# RfLink-ESPlink.net
KiCad netlist of a schematic drawn in EAGLE
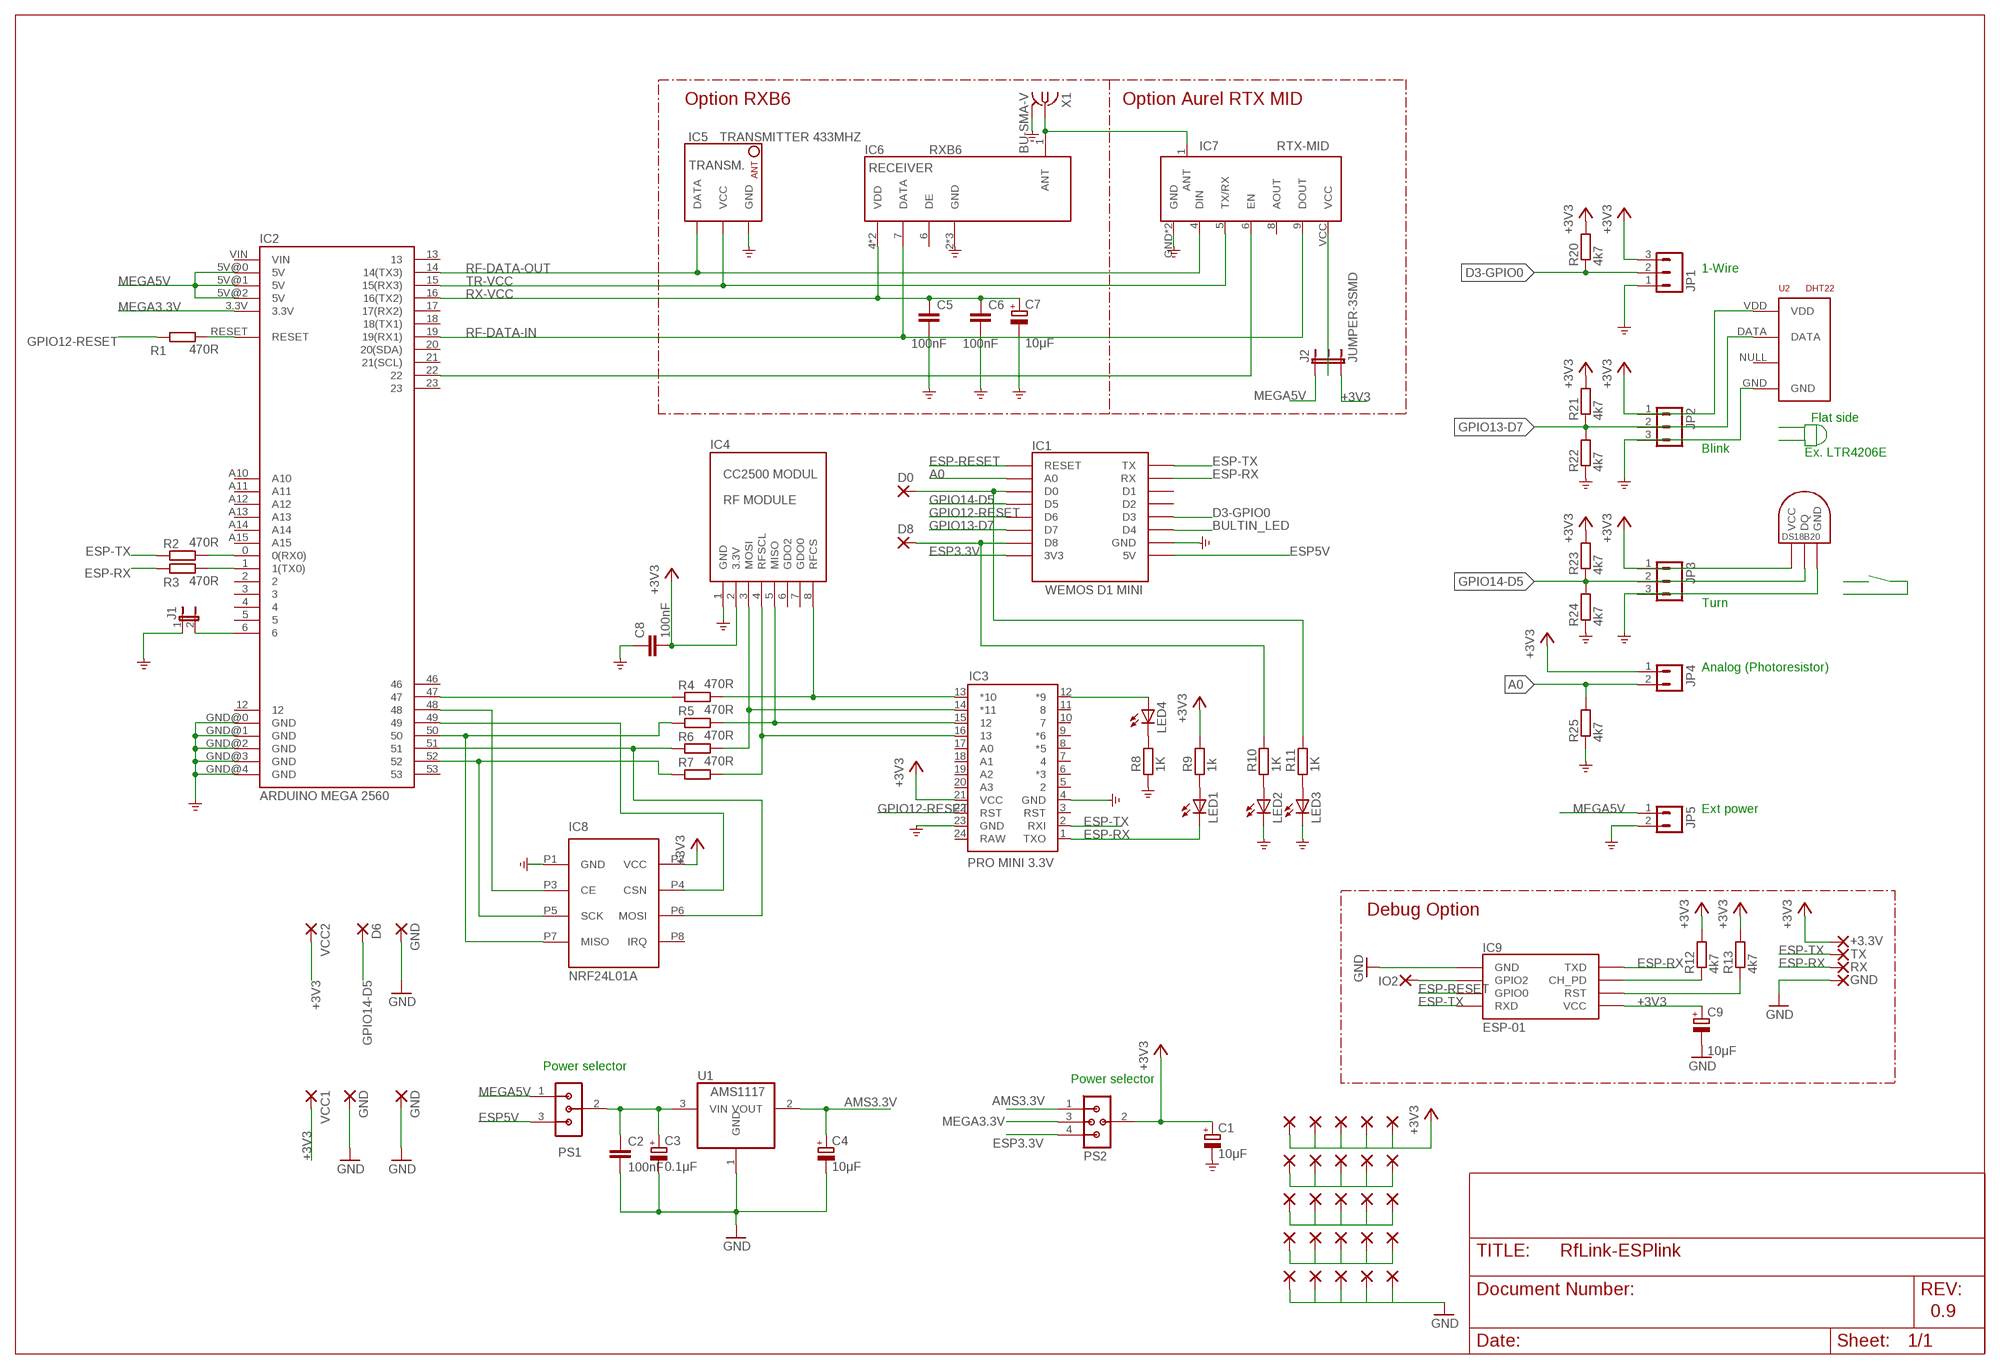
[diagram p0: schematic, sheet 1]

(export (version "E")
  (design (tool "Eeschema 10.0.6"))
  (components
    (comp (ref "+3.3V")
      (value "1,6/0,9")
      (footprint "eagle-import:1,6_0,9")
      (libsource (lib "eagle-import") (part "1,6/0,9"))
    )
    (comp (ref "C1")
      (value "10μF")
      (footprint "eagle-import:E2-5")
      (libsource (lib "eagle-import") (part "CPOL-EUE2-5"))
    )
    (comp (ref "C2")
      (value "100nF")
      (footprint "eagle-import:C0805")
      (libsource (lib "eagle-import") (part "CAPACITOR"))
    )
    (comp (ref "C3")
      (value "0.1μF")
      (footprint "eagle-import:E2-5")
      (libsource (lib "eagle-import") (part "CPOL-EUE2-5"))
    )
    (comp (ref "C4")
      (value "10μF")
      (footprint "eagle-import:E2-5")
      (libsource (lib "eagle-import") (part "CPOL-EUE2-5"))
    )
    (comp (ref "C5")
      (value "100nF")
      (footprint "eagle-import:C0805")
      (libsource (lib "eagle-import") (part "CAPACITOR"))
    )
    (comp (ref "C6")
      (value "100nF")
      (footprint "eagle-import:C0805")
      (libsource (lib "eagle-import") (part "CAPACITOR"))
    )
    (comp (ref "C7")
      (value "10μF")
      (footprint "eagle-import:E2-5")
      (libsource (lib "eagle-import") (part "CPOL-EUE2-5"))
    )
    (comp (ref "C8")
      (value "100nF")
      (footprint "eagle-import:C0805")
      (libsource (lib "eagle-import") (part "CAPACITOR"))
    )
    (comp (ref "C9")
      (value "10μF")
      (footprint "eagle-import:E2-5")
      (libsource (lib "eagle-import") (part "CPOL-EUE2-5"))
    )
    (comp (ref "D0")
      (value "1,6/0,9")
      (footprint "eagle-import:1,6_0,9")
      (libsource (lib "eagle-import") (part "1,6/0,9"))
    )
    (comp (ref "D6")
      (value "D6")
      (footprint "eagle-import:1,6_0,9")
      (libsource (lib "eagle-import") (part "1,6/0,9"))
    )
    (comp (ref "D8")
      (value "1,6/0,9")
      (footprint "eagle-import:1,6_0,9")
      (libsource (lib "eagle-import") (part "1,6/0,9"))
    )
    (comp (ref "G")
      (value "GND")
      (footprint "eagle-import:1,6_0,9")
      (libsource (lib "eagle-import") (part "1,6/0,9"))
    )
    (comp (ref "GND")
      (value "GND")
      (footprint "eagle-import:1,6_0,9")
      (libsource (lib "eagle-import") (part "1,6/0,9"))
    )
    (comp (ref "GND5")
      (value "GND")
      (footprint "eagle-import:1,6_0,9")
      (libsource (lib "eagle-import") (part "1,6/0,9"))
    )
    (comp (ref "GND7")
      (value "GND")
      (footprint "eagle-import:1,6_0,9")
      (libsource (lib "eagle-import") (part "1,6/0,9"))
    )
    (comp (ref "GPIO2")
      (value "IO2")
      (footprint "eagle-import:1,6_0,9")
      (libsource (lib "eagle-import") (part "1,6/0,9"))
    )
    (comp (ref "IC1")
      (value "WEMOS D1 MINI")
      (footprint "eagle-import:WEMOS-D1-MINI")
      (libsource (lib "eagle-import") (part "WEMOS-D1-MINI"))
    )
    (comp (ref "IC2")
      (value "ARDUINO MEGA 2560")
      (footprint "eagle-import:ARDUINO_MEGA_MINI")
      (libsource (lib "eagle-import") (part "ARDUINO-MEGA-MINI"))
    )
    (comp (ref "IC3")
      (value "PRO MINI 3.3V")
      (footprint "eagle-import:ARDUINO_PRO_MINI")
      (libsource (lib "eagle-import") (part "ARDUINO_PRO_MINI"))
    )
    (comp (ref "IC4")
      (value "CC2500 MODUL")
      (footprint "eagle-import:CC2500")
      (libsource (lib "eagle-import") (part "CC2500A-MODULE"))
    )
    (comp (ref "IC5")
      (value "TRANSMITTER 433MHZ")
      (footprint "eagle-import:TRANSMITTER433MHZ")
      (libsource (lib "eagle-import") (part "TRANSMITTER433MHZ"))
    )
    (comp (ref "IC6")
      (value "RXB6")
      (footprint "eagle-import:RXB6-LOW-SILKSCREEN")
      (libsource (lib "eagle-import") (part "HXB6-"))
    )
    (comp (ref "IC7")
      (value "RTX-MID")
      (footprint "eagle-import:RTX-MID")
      (libsource (lib "eagle-import") (part "RTX-MID"))
    )
    (comp (ref "IC8")
      (value "NRF24L01A")
      (footprint "eagle-import:NRF24L01")
      (libsource (lib "eagle-import") (part "NRF24L01A"))
    )
    (comp (ref "IC9")
      (value "ESP-01")
      (footprint "eagle-import:ESP01")
      (libsource (lib "eagle-import") (part "ESP01"))
    )
    (comp (ref "J1")
      (value "JUMPER-2SMD-NO")
      (footprint "eagle-import:SJ_2S-NO")
      (libsource (lib "eagle-import") (part "JUMPER-2SMD-NO"))
    )
    (comp (ref "J2")
      (value "JUMPER-3SMD")
      (footprint "eagle-import:SJ_3")
      (libsource (lib "eagle-import") (part "JUMPER-3SMD"))
    )
    (comp (ref "JP1")
      (value "GS015S-3.81-3P")
      (footprint "eagle-import:GS015S-3.81-3")
      (libsource (lib "eagle-import") (part "GS015S-3.81-3P"))
    )
    (comp (ref "JP2")
      (value "GS015S-3.81-3P")
      (footprint "eagle-import:GS015S-3.81-3")
      (libsource (lib "eagle-import") (part "GS015S-3.81-3P"))
    )
    (comp (ref "JP3")
      (value "GS015S-3.81-3P")
      (footprint "eagle-import:GS015S-3.81-3")
      (libsource (lib "eagle-import") (part "GS015S-3.81-3P"))
    )
    (comp (ref "JP4")
      (value "GS015S-3.81-2P")
      (footprint "eagle-import:GS015S-3.81-2")
      (libsource (lib "eagle-import") (part "GS015S-3.81-2P"))
    )
    (comp (ref "JP5")
      (value "GS015S-3.81-2P")
      (footprint "eagle-import:GS015S-3.81-2")
      (libsource (lib "eagle-import") (part "GS015S-3.81-2P"))
    )
    (comp (ref "LED1")
      (value "LED1206")
      (footprint "eagle-import:LED-1206")
      (libsource (lib "eagle-import") (part "LED1206"))
    )
    (comp (ref "LED2")
      (value "LED1206")
      (footprint "eagle-import:LED-1206")
      (libsource (lib "eagle-import") (part "LED1206"))
    )
    (comp (ref "LED3")
      (value "LED1206")
      (footprint "eagle-import:LED-1206")
      (libsource (lib "eagle-import") (part "LED1206"))
    )
    (comp (ref "LED4")
      (value "LED1206")
      (footprint "eagle-import:LED-1206")
      (libsource (lib "eagle-import") (part "LED1206"))
    )
    (comp (ref "P1")
      (value "1,6/0,9")
      (footprint "eagle-import:1,6_0,9")
      (libsource (lib "eagle-import") (part "1,6/0,9"))
    )
    (comp (ref "P2")
      (value "1,6/0,9")
      (footprint "eagle-import:1,6_0,9")
      (libsource (lib "eagle-import") (part "1,6/0,9"))
    )
    (comp (ref "P3")
      (value "1,6/0,9")
      (footprint "eagle-import:1,6_0,9")
      (libsource (lib "eagle-import") (part "1,6/0,9"))
    )
    (comp (ref "P4")
      (value "1,6/0,9")
      (footprint "eagle-import:1,6_0,9")
      (libsource (lib "eagle-import") (part "1,6/0,9"))
    )
    (comp (ref "P5")
      (value "1,6/0,9")
      (footprint "eagle-import:1,6_0,9")
      (libsource (lib "eagle-import") (part "1,6/0,9"))
    )
    (comp (ref "P6")
      (value "1,6/0,9")
      (footprint "eagle-import:1,6_0,9")
      (libsource (lib "eagle-import") (part "1,6/0,9"))
    )
    (comp (ref "P7")
      (value "1,6/0,9")
      (footprint "eagle-import:1,6_0,9")
      (libsource (lib "eagle-import") (part "1,6/0,9"))
    )
    (comp (ref "P8")
      (value "1,6/0,9")
      (footprint "eagle-import:1,6_0,9")
      (libsource (lib "eagle-import") (part "1,6/0,9"))
    )
    (comp (ref "P9")
      (value "1,6/0,9")
      (footprint "eagle-import:1,6_0,9")
      (libsource (lib "eagle-import") (part "1,6/0,9"))
    )
    (comp (ref "P10")
      (value "1,6/0,9")
      (footprint "eagle-import:1,6_0,9")
      (libsource (lib "eagle-import") (part "1,6/0,9"))
    )
    (comp (ref "P11")
      (value "1,6/0,9")
      (footprint "eagle-import:1,6_0,9")
      (libsource (lib "eagle-import") (part "1,6/0,9"))
    )
    (comp (ref "P12")
      (value "1,6/0,9")
      (footprint "eagle-import:1,6_0,9")
      (libsource (lib "eagle-import") (part "1,6/0,9"))
    )
    (comp (ref "P13")
      (value "1,6/0,9")
      (footprint "eagle-import:1,6_0,9")
      (libsource (lib "eagle-import") (part "1,6/0,9"))
    )
    (comp (ref "P14")
      (value "1,6/0,9")
      (footprint "eagle-import:1,6_0,9")
      (libsource (lib "eagle-import") (part "1,6/0,9"))
    )
    (comp (ref "P15")
      (value "1,6/0,9")
      (footprint "eagle-import:1,6_0,9")
      (libsource (lib "eagle-import") (part "1,6/0,9"))
    )
    (comp (ref "P16")
      (value "1,6/0,9")
      (footprint "eagle-import:1,6_0,9")
      (libsource (lib "eagle-import") (part "1,6/0,9"))
    )
    (comp (ref "P17")
      (value "1,6/0,9")
      (footprint "eagle-import:1,6_0,9")
      (libsource (lib "eagle-import") (part "1,6/0,9"))
    )
    (comp (ref "P18")
      (value "1,6/0,9")
      (footprint "eagle-import:1,6_0,9")
      (libsource (lib "eagle-import") (part "1,6/0,9"))
    )
    (comp (ref "P19")
      (value "1,6/0,9")
      (footprint "eagle-import:1,6_0,9")
      (libsource (lib "eagle-import") (part "1,6/0,9"))
    )
    (comp (ref "P20")
      (value "1,6/0,9")
      (footprint "eagle-import:1,6_0,9")
      (libsource (lib "eagle-import") (part "1,6/0,9"))
    )
    (comp (ref "P21")
      (value "1,6/0,9")
      (footprint "eagle-import:1,6_0,9")
      (libsource (lib "eagle-import") (part "1,6/0,9"))
    )
    (comp (ref "P22")
      (value "1,6/0,9")
      (footprint "eagle-import:1,6_0,9")
      (libsource (lib "eagle-import") (part "1,6/0,9"))
    )
    (comp (ref "P23")
      (value "1,6/0,9")
      (footprint "eagle-import:1,6_0,9")
      (libsource (lib "eagle-import") (part "1,6/0,9"))
    )
    (comp (ref "P24")
      (value "1,6/0,9")
      (footprint "eagle-import:1,6_0,9")
      (libsource (lib "eagle-import") (part "1,6/0,9"))
    )
    (comp (ref "P25")
      (value "1,6/0,9")
      (footprint "eagle-import:1,6_0,9")
      (libsource (lib "eagle-import") (part "1,6/0,9"))
    )
    (comp (ref "PS1")
      (value "SV2")
      (footprint "eagle-import:2-1")
      (libsource (lib "eagle-import") (part "2TO1POWER"))
    )
    (comp (ref "PS2")
      (value "3TO1POWER")
      (footprint "eagle-import:3-1")
      (libsource (lib "eagle-import") (part "3TO1POWER"))
    )
    (comp (ref "R1")
      (value "470R")
      (footprint "eagle-import:R0805")
      (libsource (lib "eagle-import") (part "RESISTORR0805"))
    )
    (comp (ref "R2")
      (value "470R")
      (footprint "eagle-import:R0805")
      (libsource (lib "eagle-import") (part "RESISTORR0805"))
    )
    (comp (ref "R3")
      (value "470R")
      (footprint "eagle-import:R0805")
      (libsource (lib "eagle-import") (part "RESISTORR0805"))
    )
    (comp (ref "R4")
      (value "470R")
      (footprint "eagle-import:R0805")
      (libsource (lib "eagle-import") (part "RESISTORR0805"))
    )
    (comp (ref "R5")
      (value "470R")
      (footprint "eagle-import:R0805")
      (libsource (lib "eagle-import") (part "RESISTORR0805"))
    )
    (comp (ref "R6")
      (value "470R")
      (footprint "eagle-import:R0805")
      (libsource (lib "eagle-import") (part "RESISTORR0805"))
    )
    (comp (ref "R7")
      (value "470R")
      (footprint "eagle-import:R0805")
      (libsource (lib "eagle-import") (part "RESISTORR0805"))
    )
    (comp (ref "R8")
      (value "1K")
      (footprint "eagle-import:R0805")
      (libsource (lib "eagle-import") (part "RESISTORR0805"))
    )
    (comp (ref "R9")
      (value "1k")
      (footprint "eagle-import:R0805")
      (libsource (lib "eagle-import") (part "RESISTORR0805"))
    )
    (comp (ref "R10")
      (value "1K")
      (footprint "eagle-import:R0805")
      (libsource (lib "eagle-import") (part "RESISTORR0805"))
    )
    (comp (ref "R11")
      (value "1K")
      (footprint "eagle-import:R0805")
      (libsource (lib "eagle-import") (part "RESISTORR0805"))
    )
    (comp (ref "R12")
      (value "4k7")
      (footprint "eagle-import:R0805")
      (libsource (lib "eagle-import") (part "RESISTORR0805"))
    )
    (comp (ref "R13")
      (value "4k7")
      (footprint "eagle-import:R0805")
      (libsource (lib "eagle-import") (part "RESISTORR0805"))
    )
    (comp (ref "R20")
      (value "4k7")
      (footprint "eagle-import:R0805")
      (libsource (lib "eagle-import") (part "RESISTORR0805"))
    )
    (comp (ref "R21")
      (value "4k7")
      (footprint "eagle-import:R0805")
      (libsource (lib "eagle-import") (part "RESISTORR0805"))
    )
    (comp (ref "R22")
      (value "4k7")
      (footprint "eagle-import:R0805")
      (libsource (lib "eagle-import") (part "RESISTORR0805"))
    )
    (comp (ref "R23")
      (value "4k7")
      (footprint "eagle-import:R0805")
      (libsource (lib "eagle-import") (part "RESISTORR0805"))
    )
    (comp (ref "R24")
      (value "4k7")
      (footprint "eagle-import:R0805")
      (libsource (lib "eagle-import") (part "RESISTORR0805"))
    )
    (comp (ref "R25")
      (value "4k7")
      (footprint "eagle-import:R0805")
      (libsource (lib "eagle-import") (part "RESISTORR0805"))
    )
    (comp (ref "RX")
      (value "RX")
      (footprint "eagle-import:1,6_0,9")
      (libsource (lib "eagle-import") (part "1,6/0,9"))
    )
    (comp (ref "TX")
      (value "TX")
      (footprint "eagle-import:1,6_0,9")
      (libsource (lib "eagle-import") (part "1,6/0,9"))
    )
    (comp (ref "U1")
      (value "AMS1117")
      (footprint "eagle-import:SOT223")
      (fields (field (name "MPN") "REG1117"))
      (libsource (lib "eagle-import") (part "REG1117"))
    )
    (comp (ref "U2")
      (value "DHT22")
      (footprint "eagle-import:RHT03_DHT-22")
      (libsource (lib "eagle-import") (part "RHT03_DHT-22_AM2302"))
    )
    (comp (ref "U3")
      (value "DS18B20")
      (footprint "eagle-import:DS1820")
      (libsource (lib "eagle-import") (part "DS1820TO92"))
    )
    (comp (ref "VCC1")
      (value "1,6/0,9")
      (footprint "eagle-import:1,6_0,9")
      (libsource (lib "eagle-import") (part "1,6/0,9"))
    )
    (comp (ref "VCC2")
      (value "1,6/0,9")
      (footprint "eagle-import:1,6_0,9")
      (libsource (lib "eagle-import") (part "1,6/0,9"))
    )
    (comp (ref "X1")
      (value "BU-SMA-V")
      (footprint "eagle-import:BU-SMA-V")
      (libsource (lib "eagle-import") (part "BU-SMA-V"))
    )
  )
  (nets
    (net (code "1") (name "+3V3") (class "Default")
      (node (ref "+3.3V") (pin "1") (pinfunction "P_1") (pintype "passive"))
      (node (ref "C1") (pin "+") (pinfunction "+_+") (pintype "passive"))
      (node (ref "C8") (pin "2") (pinfunction "2_2") (pintype "passive"))
      (node (ref "C9") (pin "+") (pinfunction "+_+") (pintype "passive"))
      (node (ref "IC3") (pin "21") (pinfunction "VCC_21") (pintype "bidirectional"))
      (node (ref "IC4") (pin "2") (pinfunction "3.3V_2") (pintype "bidirectional"))
      (node (ref "IC8") (pin "P2") (pinfunction "VCC_P2") (pintype "power_in"))
      (node (ref "IC9") (pin "VCC") (pinfunction "VCC_VCC") (pintype "bidirectional"))
      (node (ref "J2") (pin "3") (pinfunction "3_3") (pintype "passive"))
      (node (ref "JP1") (pin "3") (pinfunction "3_3") (pintype "passive"))
      (node (ref "JP2") (pin "1") (pinfunction "1_1") (pintype "passive"))
      (node (ref "JP3") (pin "1") (pinfunction "1_1") (pintype "passive"))
      (node (ref "JP4") (pin "1") (pinfunction "1_1") (pintype "passive"))
      (node (ref "P21") (pin "1") (pinfunction "P_1") (pintype "passive"))
      (node (ref "P22") (pin "1") (pinfunction "P_1") (pintype "passive"))
      (node (ref "P23") (pin "1") (pinfunction "P_1") (pintype "passive"))
      (node (ref "P24") (pin "1") (pinfunction "P_1") (pintype "passive"))
      (node (ref "P25") (pin "1") (pinfunction "P_1") (pintype "passive"))
      (node (ref "PS2") (pin "2") (pinfunction "2_2") (pintype "passive"))
      (node (ref "R12") (pin "2") (pinfunction "2_2") (pintype "passive"))
      (node (ref "R13") (pin "2") (pinfunction "2_2") (pintype "passive"))
      (node (ref "R20") (pin "2") (pinfunction "2_2") (pintype "passive"))
      (node (ref "R21") (pin "2") (pinfunction "2_2") (pintype "passive"))
      (node (ref "R23") (pin "2") (pinfunction "2_2") (pintype "passive"))
      (node (ref "R9") (pin "2") (pinfunction "2_2") (pintype "passive"))
      (node (ref "U2") (pin "VDD") (pinfunction "VDD_VDD") (pintype "power_in"))
      (node (ref "U3") (pin "VDD") (pinfunction "VCC_VDD") (pintype "power_in"))
      (node (ref "VCC1") (pin "1") (pinfunction "P_1") (pintype "passive"))
      (node (ref "VCC2") (pin "1") (pinfunction "P_1") (pintype "passive"))
    )
    (net (code "2") (name "/AMS3.3V") (class "Default")
      (node (ref "C4") (pin "+") (pinfunction "+_+") (pintype "passive"))
      (node (ref "PS2") (pin "1") (pinfunction "1_1") (pintype "passive"))
      (node (ref "U1") (pin "2") (pinfunction "VOUT_2") (pintype "output"))
    )
    (net (code "3") (name "/BULTIN_LED") (class "Default")
      (node (ref "IC1") (pin "D4") (pinfunction "D4_D4") (pintype "bidirectional"))
    )
    (net (code "4") (name "/ESP-RESET") (class "Default")
      (node (ref "IC1") (pin "RESET") (pinfunction "RESET_RESET") (pintype "bidirectional"))
      (node (ref "IC9") (pin "GPIO0") (pinfunction "GPIO0_GPIO0") (pintype "bidirectional"))
    )
    (net (code "5") (name "/ESP-RX") (class "Default")
      (node (ref "IC1") (pin "RX") (pinfunction "RX_RX") (pintype "bidirectional"))
      (node (ref "IC3") (pin "1") (pinfunction "TXO_1") (pintype "bidirectional"))
      (node (ref "IC9") (pin "TX") (pinfunction "TXD_TX") (pintype "bidirectional"))
      (node (ref "LED1") (pin "C") (pinfunction "C_C") (pintype "passive"))
      (node (ref "R3") (pin "1") (pinfunction "1_1") (pintype "passive"))
      (node (ref "RX") (pin "1") (pinfunction "P_1") (pintype "passive"))
    )
    (net (code "6") (name "/ESP-TX") (class "Default")
      (node (ref "IC1") (pin "TX") (pinfunction "TX_TX") (pintype "bidirectional"))
      (node (ref "IC3") (pin "2") (pinfunction "RXI_2") (pintype "bidirectional"))
      (node (ref "IC9") (pin "RX") (pinfunction "RXD_RX") (pintype "bidirectional"))
      (node (ref "R2") (pin "2") (pinfunction "2_2") (pintype "passive"))
      (node (ref "TX") (pin "1") (pinfunction "P_1") (pintype "passive"))
    )
    (net (code "7") (name "/ESP3.3V") (class "Default")
      (node (ref "IC1") (pin "3V3") (pinfunction "3V3_3V3") (pintype "bidirectional"))
      (node (ref "PS2") (pin "4") (pinfunction "4_4") (pintype "passive"))
    )
    (net (code "8") (name "/ESP5V") (class "Default")
      (node (ref "IC1") (pin "5V") (pinfunction "5V_5V") (pintype "bidirectional"))
      (node (ref "PS1") (pin "3") (pinfunction "3_3") (pintype "passive"))
    )
    (net (code "9") (name "/GPIO12-RESET") (class "Default")
      (node (ref "IC1") (pin "D6") (pinfunction "D6_D6") (pintype "bidirectional"))
      (node (ref "IC3") (pin "22") (pinfunction "RST_22") (pintype "bidirectional"))
      (node (ref "R1") (pin "2") (pinfunction "2_2") (pintype "passive"))
    )
    (net (code "10") (name "/MEGA3.3V") (class "Default")
      (node (ref "IC2") (pin "3.3V") (pinfunction "3.3V_3.3V") (pintype "bidirectional"))
      (node (ref "PS2") (pin "3") (pinfunction "3_3") (pintype "passive"))
    )
    (net (code "11") (name "/MEGA5V") (class "Default")
      (node (ref "IC2") (pin "5V@0") (pinfunction "5V_5V@0") (pintype "bidirectional"))
      (node (ref "IC2") (pin "5V@1") (pinfunction "5V_5V@1") (pintype "bidirectional"))
      (node (ref "IC2") (pin "5V@2") (pinfunction "5V_5V@2") (pintype "bidirectional"))
      (node (ref "J2") (pin "1") (pinfunction "1_1") (pintype "passive"))
      (node (ref "JP5") (pin "1") (pinfunction "1_1") (pintype "passive"))
      (node (ref "PS1") (pin "1") (pinfunction "1_1") (pintype "passive"))
    )
    (net (code "12") (name "/RF-DATA-IN") (class "Default")
      (node (ref "IC2") (pin "19") (pinfunction "19(RX1)_19") (pintype "bidirectional"))
      (node (ref "IC6") (pin "7") (pinfunction "DATA_7") (pintype "input"))
      (node (ref "IC7") (pin "9") (pinfunction "DOUT_9") (pintype "passive"))
    )
    (net (code "13") (name "/RF-DATA-OUT") (class "Default")
      (node (ref "IC2") (pin "14") (pinfunction "14(TX3)_14") (pintype "bidirectional"))
      (node (ref "IC5") (pin "P$1") (pinfunction "DATA_P$1") (pintype "input"))
      (node (ref "IC7") (pin "4") (pinfunction "DIN_4") (pintype "input"))
    )
    (net (code "14") (name "/RX-VCC") (class "Default")
      (node (ref "C5") (pin "2") (pinfunction "2_2") (pintype "passive"))
      (node (ref "C6") (pin "2") (pinfunction "2_2") (pintype "passive"))
      (node (ref "C7") (pin "+") (pinfunction "+_+") (pintype "passive"))
      (node (ref "IC2") (pin "16") (pinfunction "16(TX2)_16") (pintype "bidirectional"))
      (node (ref "IC6") (pin "4") (pinfunction "VDD_4") (pintype "power_in"))
      (node (ref "IC6") (pin "5") (pinfunction "VDD_5") (pintype "power_in"))
    )
    (net (code "15") (name "/TR-VCC") (class "Default")
      (node (ref "IC2") (pin "15") (pinfunction "15(RX3)_15") (pintype "bidirectional"))
      (node (ref "IC5") (pin "P$2") (pinfunction "VCC_P$2") (pintype "power_in"))
      (node (ref "IC7") (pin "5") (pinfunction "TX/RX_5") (pintype "passive"))
    )
    (net (code "16") (name "A0") (class "Default")
      (node (ref "IC1") (pin "A0") (pinfunction "A0_A0") (pintype "bidirectional"))
      (node (ref "JP4") (pin "2") (pinfunction "2_2") (pintype "passive"))
      (node (ref "R25") (pin "2") (pinfunction "2_2") (pintype "passive"))
    )
    (net (code "17") (name "D3-GPIO0") (class "Default")
      (node (ref "IC1") (pin "D3") (pinfunction "D3_D3") (pintype "bidirectional"))
      (node (ref "JP1") (pin "2") (pinfunction "2_2") (pintype "passive"))
      (node (ref "R20") (pin "1") (pinfunction "1_1") (pintype "passive"))
    )
    (net (code "18") (name "GND") (class "Default")
      (node (ref "C1") (pin "-") (pinfunction "-_-") (pintype "passive"))
      (node (ref "C2") (pin "2") (pinfunction "2_2") (pintype "passive"))
      (node (ref "C3") (pin "-") (pinfunction "-_-") (pintype "passive"))
      (node (ref "C4") (pin "-") (pinfunction "-_-") (pintype "passive"))
      (node (ref "C5") (pin "1") (pinfunction "1_1") (pintype "passive"))
      (node (ref "C6") (pin "1") (pinfunction "1_1") (pintype "passive"))
      (node (ref "C7") (pin "-") (pinfunction "-_-") (pintype "passive"))
      (node (ref "C8") (pin "1") (pinfunction "1_1") (pintype "passive"))
      (node (ref "C9") (pin "-") (pinfunction "-_-") (pintype "passive"))
      (node (ref "G") (pin "1") (pinfunction "P_1") (pintype "passive"))
      (node (ref "GND") (pin "1") (pinfunction "P_1") (pintype "passive"))
      (node (ref "GND5") (pin "1") (pinfunction "P_1") (pintype "passive"))
      (node (ref "GND7") (pin "1") (pinfunction "P_1") (pintype "passive"))
      (node (ref "IC1") (pin "GND") (pinfunction "GND_GND") (pintype "bidirectional"))
      (node (ref "IC2") (pin "GND@0") (pinfunction "GND_GND@0") (pintype "bidirectional"))
      (node (ref "IC2") (pin "GND@1") (pinfunction "GND_GND@1") (pintype "bidirectional"))
      (node (ref "IC2") (pin "GND@2") (pinfunction "GND_GND@2") (pintype "bidirectional"))
      (node (ref "IC2") (pin "GND@3") (pinfunction "GND_GND@3") (pintype "bidirectional"))
      (node (ref "IC2") (pin "GND@4") (pinfunction "GND_GND@4") (pintype "bidirectional"))
      (node (ref "IC3") (pin "23") (pinfunction "GND_23") (pintype "bidirectional"))
      (node (ref "IC3") (pin "4") (pinfunction "GND_4") (pintype "bidirectional"))
      (node (ref "IC4") (pin "1") (pinfunction "GND_1") (pintype "bidirectional"))
      (node (ref "IC5") (pin "P$3") (pinfunction "GND_P$3") (pintype "power_in"))
      (node (ref "IC6") (pin "2") (pinfunction "GND_2") (pintype "power_in"))
      (node (ref "IC6") (pin "3") (pinfunction "GND_3") (pintype "power_in"))
      (node (ref "IC6") (pin "8") (pinfunction "GND_8") (pintype "power_in"))
      (node (ref "IC7") (pin "GND") (pinfunction "GND_GND") (pintype "passive"))
      (node (ref "IC7") (pin "GND1") (pinfunction "GND_GND1") (pintype "passive"))
      (node (ref "IC8") (pin "P1") (pinfunction "GND_P1") (pintype "input"))
      (node (ref "IC9") (pin "GND") (pinfunction "GND_GND") (pintype "bidirectional"))
      (node (ref "J1") (pin "1") (pinfunction "1_1") (pintype "passive"))
      (node (ref "JP1") (pin "1") (pinfunction "1_1") (pintype "passive"))
      (node (ref "JP2") (pin "3") (pinfunction "3_3") (pintype "passive"))
      (node (ref "JP3") (pin "3") (pinfunction "3_3") (pintype "passive"))
      (node (ref "JP5") (pin "2") (pinfunction "2_2") (pintype "passive"))
      (node (ref "LED2") (pin "C") (pinfunction "C_C") (pintype "passive"))
      (node (ref "LED3") (pin "C") (pinfunction "C_C") (pintype "passive"))
      (node (ref "P11") (pin "1") (pinfunction "P_1") (pintype "passive"))
      (node (ref "P12") (pin "1") (pinfunction "P_1") (pintype "passive"))
      (node (ref "P13") (pin "1") (pinfunction "P_1") (pintype "passive"))
      (node (ref "P14") (pin "1") (pinfunction "P_1") (pintype "passive"))
      (node (ref "P15") (pin "1") (pinfunction "P_1") (pintype "passive"))
      (node (ref "R22") (pin "1") (pinfunction "1_1") (pintype "passive"))
      (node (ref "R24") (pin "1") (pinfunction "1_1") (pintype "passive"))
      (node (ref "R25") (pin "1") (pinfunction "1_1") (pintype "passive"))
      (node (ref "R8") (pin "1") (pinfunction "1_1") (pintype "passive"))
      (node (ref "U1") (pin "1") (pinfunction "GND_1") (pintype "power_in"))
      (node (ref "U2") (pin "GND") (pinfunction "GND_GND") (pintype "power_in"))
      (node (ref "U3") (pin "GND") (pinfunction "GND_GND") (pintype "power_in"))
      (node (ref "X1") (pin "2") (pinfunction "2_2") (pintype "passive"))
      (node (ref "X1") (pin "3") (pinfunction "2_3") (pintype "passive"))
      (node (ref "X1") (pin "4") (pinfunction "2_4") (pintype "passive"))
      (node (ref "X1") (pin "5") (pinfunction "2_5") (pintype "passive"))
    )
    (net (code "19") (name "GPIO13-D7") (class "Default")
      (node (ref "IC1") (pin "D7") (pinfunction "D7_D7") (pintype "bidirectional"))
      (node (ref "JP2") (pin "2") (pinfunction "2_2") (pintype "passive"))
      (node (ref "R21") (pin "1") (pinfunction "1_1") (pintype "passive"))
      (node (ref "R22") (pin "2") (pinfunction "2_2") (pintype "passive"))
      (node (ref "U2") (pin "DATA") (pinfunction "DATA_DATA") (pintype "bidirectional"))
    )
    (net (code "20") (name "GPIO14-D5") (class "Default")
      (node (ref "D6") (pin "1") (pinfunction "P_1") (pintype "passive"))
      (node (ref "IC1") (pin "D5") (pinfunction "D5_D5") (pintype "bidirectional"))
      (node (ref "JP3") (pin "2") (pinfunction "2_2") (pintype "passive"))
      (node (ref "R23") (pin "1") (pinfunction "1_1") (pintype "passive"))
      (node (ref "R24") (pin "2") (pinfunction "2_2") (pintype "passive"))
      (node (ref "U3") (pin "DQ") (pinfunction "DQ_DQ") (pintype "bidirectional"))
    )
    (net (code "21") (name "Net-(D0-P)") (class "Default")
      (node (ref "D0") (pin "1") (pinfunction "P_1") (pintype "passive"))
      (node (ref "IC1") (pin "D0") (pinfunction "D0_D0") (pintype "bidirectional"))
      (node (ref "R11") (pin "2") (pinfunction "2_2") (pintype "passive"))
    )
    (net (code "22") (name "Net-(D8-P)") (class "Default")
      (node (ref "D8") (pin "1") (pinfunction "P_1") (pintype "passive"))
      (node (ref "IC1") (pin "D8") (pinfunction "D8_D8") (pintype "bidirectional"))
      (node (ref "R10") (pin "2") (pinfunction "2_2") (pintype "passive"))
    )
    (net (code "23") (name "Net-(GPIO2-P)") (class "Default")
      (node (ref "GPIO2") (pin "1") (pinfunction "P_1") (pintype "passive"))
      (node (ref "IC9") (pin "GPIO2") (pinfunction "GPIO2_GPIO2") (pintype "bidirectional"))
    )
    (net (code "24") (name "Net-(IC2-0(RX0))") (class "Default")
      (node (ref "IC2") (pin "0") (pinfunction "0(RX0)_0") (pintype "bidirectional"))
      (node (ref "R2") (pin "1") (pinfunction "1_1") (pintype "passive"))
    )
    (net (code "25") (name "Net-(IC2-1(TX0))") (class "Default")
      (node (ref "IC2") (pin "1") (pinfunction "1(TX0)_1") (pintype "bidirectional"))
      (node (ref "R3") (pin "2") (pinfunction "2_2") (pintype "passive"))
    )
    (net (code "26") (name "Net-(IC2-Pad6)") (class "Default")
      (node (ref "IC2") (pin "6") (pinfunction "6_6") (pintype "bidirectional"))
      (node (ref "J1") (pin "2") (pinfunction "2_2") (pintype "passive"))
    )
    (net (code "27") (name "Net-(IC2-Pad47)") (class "Default")
      (node (ref "IC2") (pin "47") (pinfunction "47_47") (pintype "bidirectional"))
      (node (ref "R4") (pin "1") (pinfunction "1_1") (pintype "passive"))
    )
    (net (code "28") (name "Net-(IC2-PadRESET)") (class "Default")
      (node (ref "IC2") (pin "RESET") (pinfunction "RESET_RESET") (pintype "bidirectional"))
      (node (ref "R1") (pin "1") (pinfunction "1_1") (pintype "passive"))
    )
    (net (code "29") (name "Net-(IC3-*9)") (class "Default")
      (node (ref "IC3") (pin "12") (pinfunction "*9_12") (pintype "bidirectional"))
      (node (ref "LED4") (pin "A") (pinfunction "A_A") (pintype "passive"))
    )
    (net (code "30") (name "Net-(IC3-*10)") (class "Default")
      (node (ref "IC3") (pin "13") (pinfunction "*10_13") (pintype "bidirectional"))
      (node (ref "IC4") (pin "8") (pinfunction "RFCS_8") (pintype "bidirectional"))
      (node (ref "R4") (pin "2") (pinfunction "2_2") (pintype "passive"))
    )
    (net (code "31") (name "Net-(IC3-*11)") (class "Default")
      (node (ref "IC3") (pin "14") (pinfunction "*11_14") (pintype "bidirectional"))
      (node (ref "IC4") (pin "3") (pinfunction "MOSI_3") (pintype "bidirectional"))
      (node (ref "R6") (pin "2") (pinfunction "2_2") (pintype "passive"))
    )
    (net (code "32") (name "Net-(IC3-12)") (class "Default")
      (node (ref "IC3") (pin "15") (pinfunction "12_15") (pintype "bidirectional"))
      (node (ref "IC4") (pin "5") (pinfunction "MISO_5") (pintype "bidirectional"))
      (node (ref "R5") (pin "2") (pinfunction "2_2") (pintype "passive"))
    )
    (net (code "33") (name "Net-(IC3-13)") (class "Default")
      (node (ref "IC3") (pin "16") (pinfunction "13_16") (pintype "bidirectional"))
      (node (ref "IC4") (pin "4") (pinfunction "RFSCL_4") (pintype "bidirectional"))
      (node (ref "R7") (pin "2") (pinfunction "2_2") (pintype "passive"))
    )
    (net (code "34") (name "Net-(IC6-ANT)") (class "Default")
      (node (ref "IC6") (pin "1") (pinfunction "ANT_1") (pintype "output"))
      (node (ref "IC7") (pin "1") (pinfunction "ANT_1") (pintype "passive"))
      (node (ref "X1") (pin "1") (pinfunction "1_1") (pintype "passive"))
    )
    (net (code "35") (name "Net-(IC7-EN)") (class "Default")
      (node (ref "IC2") (pin "22") (pinfunction "22_22") (pintype "bidirectional"))
      (node (ref "IC7") (pin "6") (pinfunction "EN_6") (pintype "passive"))
    )
    (net (code "36") (name "Net-(IC7-PadVCC)") (class "Default")
      (node (ref "IC7") (pin "VCC") (pinfunction "VCC_VCC") (pintype "passive"))
      (node (ref "J2") (pin "2") (pinfunction "2_2") (pintype "passive"))
    )
    (net (code "37") (name "Net-(IC8-CE)") (class "Default")
      (node (ref "IC2") (pin "48") (pinfunction "48_48") (pintype "bidirectional"))
      (node (ref "IC8") (pin "P3") (pinfunction "CE_P3") (pintype "bidirectional"))
    )
    (net (code "38") (name "Net-(IC8-CSN)") (class "Default")
      (node (ref "IC2") (pin "49") (pinfunction "49_49") (pintype "bidirectional"))
      (node (ref "IC8") (pin "P4") (pinfunction "CSN_P4") (pintype "bidirectional"))
    )
    (net (code "39") (name "Net-(IC8-MISO)") (class "Default")
      (node (ref "IC2") (pin "50") (pinfunction "50_50") (pintype "bidirectional"))
      (node (ref "IC8") (pin "P7") (pinfunction "MISO_P7") (pintype "bidirectional"))
      (node (ref "R5") (pin "1") (pinfunction "1_1") (pintype "passive"))
    )
    (net (code "40") (name "Net-(IC8-MOSI)") (class "Default")
      (node (ref "IC2") (pin "51") (pinfunction "51_51") (pintype "bidirectional"))
      (node (ref "IC8") (pin "P6") (pinfunction "MOSI_P6") (pintype "bidirectional"))
      (node (ref "R6") (pin "1") (pinfunction "1_1") (pintype "passive"))
    )
    (net (code "41") (name "Net-(IC8-SCK)") (class "Default")
      (node (ref "IC2") (pin "52") (pinfunction "52_52") (pintype "bidirectional"))
      (node (ref "IC8") (pin "P5") (pinfunction "SCK_P5") (pintype "bidirectional"))
      (node (ref "R7") (pin "1") (pinfunction "1_1") (pintype "passive"))
    )
    (net (code "42") (name "Net-(IC9-PadCH_PD)") (class "Default")
      (node (ref "IC9") (pin "CH_PD") (pinfunction "CH_PD_CH_PD") (pintype "bidirectional"))
      (node (ref "R12") (pin "1") (pinfunction "1_1") (pintype "passive"))
    )
    (net (code "43") (name "Net-(IC9-PadRST)") (class "Default")
      (node (ref "IC9") (pin "RST") (pinfunction "RST_RST") (pintype "bidirectional"))
      (node (ref "R13") (pin "1") (pinfunction "1_1") (pintype "passive"))
    )
    (net (code "44") (name "Net-(LED1-PadA)") (class "Default")
      (node (ref "LED1") (pin "A") (pinfunction "A_A") (pintype "passive"))
      (node (ref "R9") (pin "1") (pinfunction "1_1") (pintype "passive"))
    )
    (net (code "45") (name "Net-(LED2-PadA)") (class "Default")
      (node (ref "LED2") (pin "A") (pinfunction "A_A") (pintype "passive"))
      (node (ref "R10") (pin "1") (pinfunction "1_1") (pintype "passive"))
    )
    (net (code "46") (name "Net-(LED3-PadA)") (class "Default")
      (node (ref "LED3") (pin "A") (pinfunction "A_A") (pintype "passive"))
      (node (ref "R11") (pin "1") (pinfunction "1_1") (pintype "passive"))
    )
    (net (code "47") (name "Net-(LED4-PadC)") (class "Default")
      (node (ref "LED4") (pin "C") (pinfunction "C_C") (pintype "passive"))
      (node (ref "R8") (pin "2") (pinfunction "2_2") (pintype "passive"))
    )
    (net (code "48") (name "Net-(P1-P)") (class "Default")
      (node (ref "P1") (pin "1") (pinfunction "P_1") (pintype "passive"))
      (node (ref "P2") (pin "1") (pinfunction "P_1") (pintype "passive"))
      (node (ref "P3") (pin "1") (pinfunction "P_1") (pintype "passive"))
      (node (ref "P4") (pin "1") (pinfunction "P_1") (pintype "passive"))
      (node (ref "P5") (pin "1") (pinfunction "P_1") (pintype "passive"))
    )
    (net (code "49") (name "Net-(P10-P)") (class "Default")
      (node (ref "P10") (pin "1") (pinfunction "P_1") (pintype "passive"))
      (node (ref "P6") (pin "1") (pinfunction "P_1") (pintype "passive"))
      (node (ref "P7") (pin "1") (pinfunction "P_1") (pintype "passive"))
      (node (ref "P8") (pin "1") (pinfunction "P_1") (pintype "passive"))
      (node (ref "P9") (pin "1") (pinfunction "P_1") (pintype "passive"))
    )
    (net (code "50") (name "Net-(P16-P)") (class "Default")
      (node (ref "P16") (pin "1") (pinfunction "P_1") (pintype "passive"))
      (node (ref "P17") (pin "1") (pinfunction "P_1") (pintype "passive"))
      (node (ref "P18") (pin "1") (pinfunction "P_1") (pintype "passive"))
      (node (ref "P19") (pin "1") (pinfunction "P_1") (pintype "passive"))
      (node (ref "P20") (pin "1") (pinfunction "P_1") (pintype "passive"))
    )
    (net (code "51") (name "Net-(U1-VIN)") (class "Default")
      (node (ref "C2") (pin "1") (pinfunction "1_1") (pintype "passive"))
      (node (ref "C3") (pin "+") (pinfunction "+_+") (pintype "passive"))
      (node (ref "PS1") (pin "2") (pinfunction "2_2") (pintype "passive"))
      (node (ref "U1") (pin "3") (pinfunction "VIN_3") (pintype "input"))
    )
    (net (code "52") (name "unconnected-(IC1-PadD1)") (class "Default")
      (node (ref "IC1") (pin "D1") (pinfunction "D1_D1") (pintype "bidirectional"))
    )
    (net (code "53") (name "unconnected-(IC1-PadD2)") (class "Default")
      (node (ref "IC1") (pin "D2") (pinfunction "D2_D2") (pintype "bidirectional"))
    )
    (net (code "54") (name "unconnected-(IC2-17(RX2)-Pad17)") (class "Default")
      (node (ref "IC2") (pin "17") (pinfunction "17(RX2)_17") (pintype "bidirectional"))
    )
    (net (code "55") (name "unconnected-(IC2-18(TX1)-Pad18)") (class "Default")
      (node (ref "IC2") (pin "18") (pinfunction "18(TX1)_18") (pintype "bidirectional"))
    )
    (net (code "56") (name "unconnected-(IC2-20(SDA)-Pad20)") (class "Default")
      (node (ref "IC2") (pin "20") (pinfunction "20(SDA)_20") (pintype "bidirectional"))
    )
    (net (code "57") (name "unconnected-(IC2-21(SCL)-Pad21)") (class "Default")
      (node (ref "IC2") (pin "21") (pinfunction "21(SCL)_21") (pintype "bidirectional"))
    )
    (net (code "58") (name "unconnected-(IC2-Pad2)") (class "Default")
      (node (ref "IC2") (pin "2") (pinfunction "2_2") (pintype "bidirectional"))
    )
    (net (code "59") (name "unconnected-(IC2-Pad3)") (class "Default")
      (node (ref "IC2") (pin "3") (pinfunction "3_3") (pintype "bidirectional"))
    )
    (net (code "60") (name "unconnected-(IC2-Pad4)") (class "Default")
      (node (ref "IC2") (pin "4") (pinfunction "4_4") (pintype "bidirectional"))
    )
    (net (code "61") (name "unconnected-(IC2-Pad5)") (class "Default")
      (node (ref "IC2") (pin "5") (pinfunction "5_5") (pintype "bidirectional"))
    )
    (net (code "62") (name "unconnected-(IC2-Pad12)") (class "Default")
      (node (ref "IC2") (pin "12") (pinfunction "12_12") (pintype "bidirectional"))
    )
    (net (code "63") (name "unconnected-(IC2-Pad13)") (class "Default")
      (node (ref "IC2") (pin "13") (pinfunction "13_13") (pintype "bidirectional"))
    )
    (net (code "64") (name "unconnected-(IC2-Pad23)") (class "Default")
      (node (ref "IC2") (pin "23") (pinfunction "23_23") (pintype "bidirectional"))
    )
    (net (code "65") (name "unconnected-(IC2-Pad46)") (class "Default")
      (node (ref "IC2") (pin "46") (pinfunction "46_46") (pintype "bidirectional"))
    )
    (net (code "66") (name "unconnected-(IC2-Pad53)") (class "Default")
      (node (ref "IC2") (pin "53") (pinfunction "53_53") (pintype "bidirectional"))
    )
    (net (code "67") (name "unconnected-(IC2-PadA10)") (class "Default")
      (node (ref "IC2") (pin "A10") (pinfunction "A10_A10") (pintype "bidirectional"))
    )
    (net (code "68") (name "unconnected-(IC2-PadA11)") (class "Default")
      (node (ref "IC2") (pin "A11") (pinfunction "A11_A11") (pintype "bidirectional"))
    )
    (net (code "69") (name "unconnected-(IC2-PadA12)") (class "Default")
      (node (ref "IC2") (pin "A12") (pinfunction "A12_A12") (pintype "bidirectional"))
    )
    (net (code "70") (name "unconnected-(IC2-PadA13)") (class "Default")
      (node (ref "IC2") (pin "A13") (pinfunction "A13_A13") (pintype "bidirectional"))
    )
    (net (code "71") (name "unconnected-(IC2-PadA14)") (class "Default")
      (node (ref "IC2") (pin "A14") (pinfunction "A14_A14") (pintype "bidirectional"))
    )
    (net (code "72") (name "unconnected-(IC2-PadA15)") (class "Default")
      (node (ref "IC2") (pin "A15") (pinfunction "A15_A15") (pintype "bidirectional"))
    )
    (net (code "73") (name "unconnected-(IC2-PadVIN)") (class "Default")
      (node (ref "IC2") (pin "VIN") (pinfunction "VIN_VIN") (pintype "bidirectional"))
    )
    (net (code "74") (name "unconnected-(IC3-*3-Pad6)") (class "Default")
      (node (ref "IC3") (pin "6") (pinfunction "*3_6") (pintype "bidirectional"))
    )
    (net (code "75") (name "unconnected-(IC3-*5-Pad8)") (class "Default")
      (node (ref "IC3") (pin "8") (pinfunction "*5_8") (pintype "bidirectional"))
    )
    (net (code "76") (name "unconnected-(IC3-*6-Pad9)") (class "Default")
      (node (ref "IC3") (pin "9") (pinfunction "*6_9") (pintype "bidirectional"))
    )
    (net (code "77") (name "unconnected-(IC3-2-Pad5)") (class "Default")
      (node (ref "IC3") (pin "5") (pinfunction "2_5") (pintype "bidirectional"))
    )
    (net (code "78") (name "unconnected-(IC3-4-Pad7)") (class "Default")
      (node (ref "IC3") (pin "7") (pinfunction "4_7") (pintype "bidirectional"))
    )
    (net (code "79") (name "unconnected-(IC3-7-Pad10)") (class "Default")
      (node (ref "IC3") (pin "10") (pinfunction "7_10") (pintype "bidirectional"))
    )
    (net (code "80") (name "unconnected-(IC3-8-Pad11)") (class "Default")
      (node (ref "IC3") (pin "11") (pinfunction "8_11") (pintype "bidirectional"))
    )
    (net (code "81") (name "unconnected-(IC3-A0-Pad17)") (class "Default")
      (node (ref "IC3") (pin "17") (pinfunction "A0_17") (pintype "bidirectional"))
    )
    (net (code "82") (name "unconnected-(IC3-A1-Pad18)") (class "Default")
      (node (ref "IC3") (pin "18") (pinfunction "A1_18") (pintype "bidirectional"))
    )
    (net (code "83") (name "unconnected-(IC3-A2-Pad19)") (class "Default")
      (node (ref "IC3") (pin "19") (pinfunction "A2_19") (pintype "bidirectional"))
    )
    (net (code "84") (name "unconnected-(IC3-A3-Pad20)") (class "Default")
      (node (ref "IC3") (pin "20") (pinfunction "A3_20") (pintype "bidirectional"))
    )
    (net (code "85") (name "unconnected-(IC3-RAW-Pad24)") (class "Default")
      (node (ref "IC3") (pin "24") (pinfunction "RAW_24") (pintype "bidirectional"))
    )
    (net (code "86") (name "unconnected-(IC3-RST-Pad3)") (class "Default")
      (node (ref "IC3") (pin "3") (pinfunction "RST_3") (pintype "bidirectional"))
    )
    (net (code "87") (name "unconnected-(IC4-GDO0-Pad7)") (class "Default")
      (node (ref "IC4") (pin "7") (pinfunction "GDO0_7") (pintype "bidirectional"))
    )
    (net (code "88") (name "unconnected-(IC4-GDO2-Pad6)") (class "Default")
      (node (ref "IC4") (pin "6") (pinfunction "GDO2_6") (pintype "bidirectional"))
    )
    (net (code "89") (name "unconnected-(IC6-DE-Pad6)") (class "Default")
      (node (ref "IC6") (pin "6") (pinfunction "DE_6") (pintype "bidirectional"))
    )
    (net (code "90") (name "unconnected-(IC7-AOUT-Pad8)") (class "Default")
      (node (ref "IC7") (pin "8") (pinfunction "AOUT_8") (pintype "passive"))
    )
    (net (code "91") (name "unconnected-(IC8-IRQ-PadP8)") (class "Default")
      (node (ref "IC8") (pin "P8") (pinfunction "IRQ_P8") (pintype "bidirectional"))
    )
    (net (code "92") (name "unconnected-(U2-PadNULL)") (class "Default")
      (node (ref "U2") (pin "NULL") (pinfunction "NULL_NULL") (pintype "no_connect"))
    )
  )
)
